# mainboardv3_1-clone.net
KiCad netlist of a schematic drawn in EAGLE
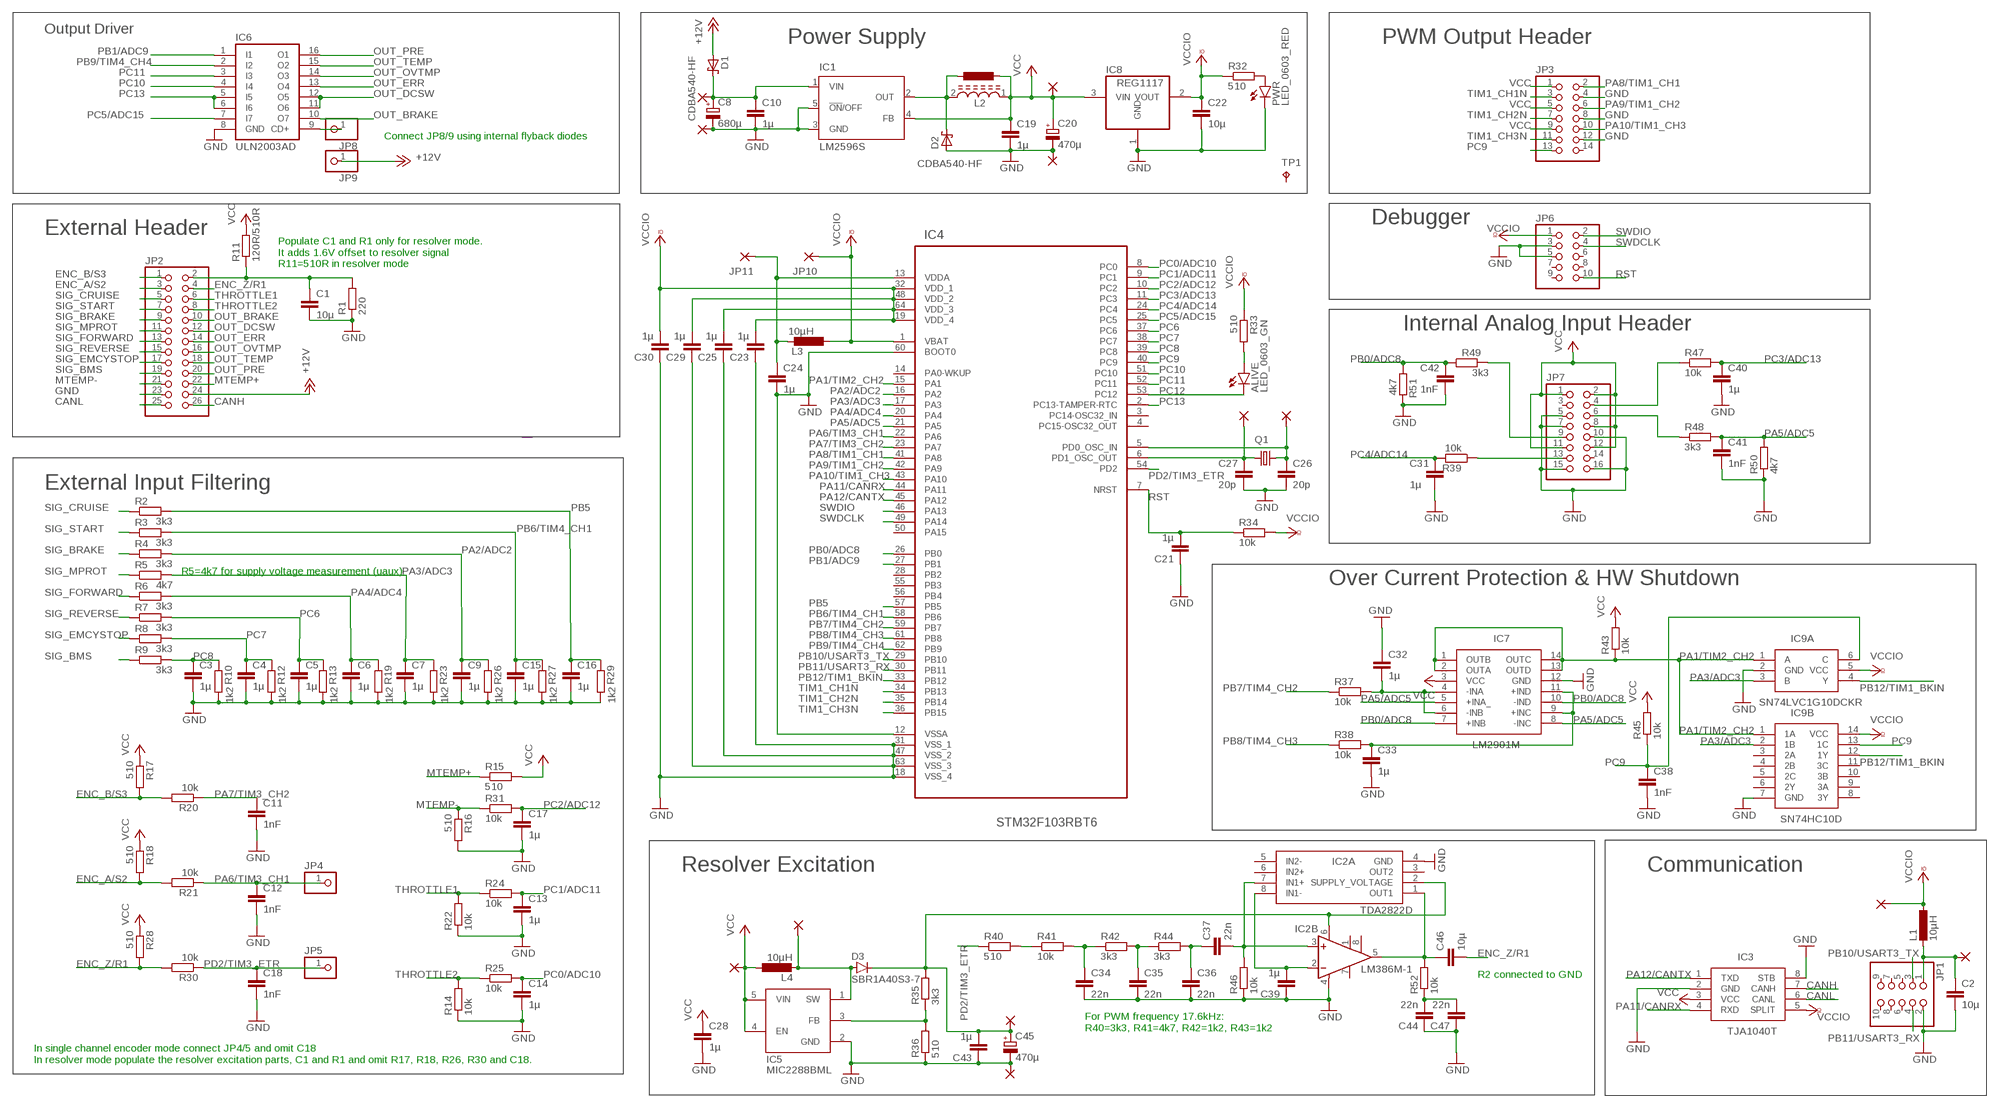
[diagram p0: schematic, sheet 1]

(export (version "E")
  (design (tool "Eeschema 10.0.6"))
  (components
    (comp (ref "ALIVE")
      (value "LED_0603_GN")
      (footprint "eagle-import:SML0805")
      (libsource (lib "eagle-import") (part "LEDSML0805"))
    )
    (comp (ref "C1")
      (value "10µ")
      (footprint "eagle-import:C0805K")
      (libsource (lib "eagle-import") (part "C-EUC0805K"))
    )
    (comp (ref "C2")
      (value "10µ")
      (footprint "eagle-import:C0805K")
      (libsource (lib "eagle-import") (part "C-EUC0805K"))
    )
    (comp (ref "C3")
      (value "1µ")
      (footprint "eagle-import:C0603K")
      (libsource (lib "eagle-import") (part "C-EUC0603K"))
    )
    (comp (ref "C4")
      (value "1µ")
      (footprint "eagle-import:C0603K")
      (libsource (lib "eagle-import") (part "C-EUC0603K"))
    )
    (comp (ref "C5")
      (value "1µ")
      (footprint "eagle-import:C0603K")
      (libsource (lib "eagle-import") (part "C-EUC0603K"))
    )
    (comp (ref "C6")
      (value "1µ")
      (footprint "eagle-import:C0603K")
      (libsource (lib "eagle-import") (part "C-EUC0603K"))
    )
    (comp (ref "C7")
      (value "1µ")
      (footprint "eagle-import:C0603K")
      (libsource (lib "eagle-import") (part "C-EUC0603K"))
    )
    (comp (ref "C8")
      (value "680µ")
      (footprint "eagle-import:153CLV-1014")
      (libsource (lib "eagle-import") (part "CPOL-EU153CLV-1014"))
    )
    (comp (ref "C9")
      (value "1µ")
      (footprint "eagle-import:C0603K")
      (libsource (lib "eagle-import") (part "C-EUC0603K"))
    )
    (comp (ref "C10")
      (value "1µ")
      (footprint "eagle-import:C0603K")
      (libsource (lib "eagle-import") (part "C-EUC0603K"))
    )
    (comp (ref "C11")
      (value "1nF")
      (footprint "eagle-import:C0603K")
      (libsource (lib "eagle-import") (part "C-EUC0603K"))
    )
    (comp (ref "C12")
      (value "1nF")
      (footprint "eagle-import:C0603K")
      (libsource (lib "eagle-import") (part "C-EUC0603K"))
    )
    (comp (ref "C13")
      (value "1µ")
      (footprint "eagle-import:C0603K")
      (libsource (lib "eagle-import") (part "C-EUC0603K"))
    )
    (comp (ref "C14")
      (value "1µ")
      (footprint "eagle-import:C0603K")
      (libsource (lib "eagle-import") (part "C-EUC0603K"))
    )
    (comp (ref "C15")
      (value "1µ")
      (footprint "eagle-import:C0603K")
      (libsource (lib "eagle-import") (part "C-EUC0603K"))
    )
    (comp (ref "C16")
      (value "1µ")
      (footprint "eagle-import:C0603K")
      (libsource (lib "eagle-import") (part "C-EUC0603K"))
    )
    (comp (ref "C17")
      (value "1µ")
      (footprint "eagle-import:C0603K")
      (libsource (lib "eagle-import") (part "C-EUC0603K"))
    )
    (comp (ref "C18")
      (value "1nF")
      (footprint "eagle-import:C0603K")
      (libsource (lib "eagle-import") (part "C-EUC0603K"))
    )
    (comp (ref "C19")
      (value "1µ")
      (footprint "eagle-import:C0603K")
      (libsource (lib "eagle-import") (part "C-EUC0603K"))
    )
    (comp (ref "C20")
      (value "470µ")
      (footprint "eagle-import:153CLV-0605")
      (libsource (lib "eagle-import") (part "CPOL-EU153CLV-0605"))
    )
    (comp (ref "C21")
      (value "1µ")
      (footprint "eagle-import:C0603K")
      (libsource (lib "eagle-import") (part "C-EUC0603K"))
    )
    (comp (ref "C22")
      (value "10µ")
      (footprint "eagle-import:C0805K")
      (libsource (lib "eagle-import") (part "C-EUC0805K"))
    )
    (comp (ref "C23")
      (value "1µ")
      (footprint "eagle-import:C0603K")
      (libsource (lib "eagle-import") (part "C-EUC0603K"))
    )
    (comp (ref "C24")
      (value "1µ")
      (footprint "eagle-import:C0603K")
      (libsource (lib "eagle-import") (part "C-EUC0603K"))
    )
    (comp (ref "C25")
      (value "1µ")
      (footprint "eagle-import:C0603K")
      (libsource (lib "eagle-import") (part "C-EUC0603K"))
    )
    (comp (ref "C26")
      (value "20p")
      (footprint "eagle-import:C0603K")
      (libsource (lib "eagle-import") (part "C-EUC0603K"))
    )
    (comp (ref "C27")
      (value "20p")
      (footprint "eagle-import:C0603K")
      (libsource (lib "eagle-import") (part "C-EUC0603K"))
    )
    (comp (ref "C28")
      (value "1µ")
      (footprint "eagle-import:C0603K")
      (libsource (lib "eagle-import") (part "C-EUC0603K"))
    )
    (comp (ref "C29")
      (value "1µ")
      (footprint "eagle-import:C0603K")
      (libsource (lib "eagle-import") (part "C-EUC0603K"))
    )
    (comp (ref "C30")
      (value "1µ")
      (footprint "eagle-import:C0603K")
      (libsource (lib "eagle-import") (part "C-EUC0603K"))
    )
    (comp (ref "C31")
      (value "1µ")
      (footprint "eagle-import:C0603K")
      (libsource (lib "eagle-import") (part "C-EUC0603K"))
    )
    (comp (ref "C32")
      (value "1µ")
      (footprint "eagle-import:C0603K")
      (libsource (lib "eagle-import") (part "C-EUC0603K"))
    )
    (comp (ref "C33")
      (value "1µ")
      (footprint "eagle-import:C0603K")
      (libsource (lib "eagle-import") (part "C-EUC0603K"))
    )
    (comp (ref "C34")
      (value "22n")
      (footprint "eagle-import:C0603K")
      (libsource (lib "eagle-import") (part "C-EUC0603K"))
    )
    (comp (ref "C35")
      (value "22n")
      (footprint "eagle-import:C0603K")
      (libsource (lib "eagle-import") (part "C-EUC0603K"))
    )
    (comp (ref "C36")
      (value "22n")
      (footprint "eagle-import:C0603K")
      (libsource (lib "eagle-import") (part "C-EUC0603K"))
    )
    (comp (ref "C37")
      (value "22n")
      (footprint "eagle-import:C0603K")
      (libsource (lib "eagle-import") (part "C-EUC0603K"))
    )
    (comp (ref "C38")
      (value "1nF")
      (footprint "eagle-import:C0603K")
      (libsource (lib "eagle-import") (part "C-EUC0603K"))
    )
    (comp (ref "C39")
      (value "1µ")
      (footprint "eagle-import:C0603K")
      (libsource (lib "eagle-import") (part "C-EUC0603K"))
    )
    (comp (ref "C40")
      (value "1µ")
      (footprint "eagle-import:C0603K")
      (libsource (lib "eagle-import") (part "C-EUC0603K"))
    )
    (comp (ref "C41")
      (value "1nF")
      (footprint "eagle-import:C0603K")
      (libsource (lib "eagle-import") (part "C-EUC0603K"))
    )
    (comp (ref "C42")
      (value "1nF")
      (footprint "eagle-import:C0603K")
      (libsource (lib "eagle-import") (part "C-EUC0603K"))
    )
    (comp (ref "C43")
      (value "1µ")
      (footprint "eagle-import:C0603K")
      (libsource (lib "eagle-import") (part "C-EUC0603K"))
    )
    (comp (ref "C44")
      (value "22n")
      (footprint "eagle-import:C0603K")
      (libsource (lib "eagle-import") (part "C-EUC0603K"))
    )
    (comp (ref "C45")
      (value "470µ")
      (footprint "eagle-import:153CLV-0605")
      (libsource (lib "eagle-import") (part "CPOL-EU153CLV-0605"))
    )
    (comp (ref "C46")
      (value "10µ")
      (footprint "eagle-import:C0805K")
      (libsource (lib "eagle-import") (part "C-EUC0805K"))
    )
    (comp (ref "C47")
      (value "22n")
      (footprint "eagle-import:C0603K")
      (libsource (lib "eagle-import") (part "C-EUC0603K"))
    )
    (comp (ref "D1")
      (value "CDBA540-HF")
      (footprint "eagle-import:SMB")
      (libsource (lib "eagle-import") (part "SCHOTTKY-DIODESMD"))
    )
    (comp (ref "D2")
      (value "CDBA540-HF")
      (footprint "eagle-import:SMB")
      (libsource (lib "eagle-import") (part "SCHOTTKY-DIODESMD"))
    )
    (comp (ref "D3")
      (value "SBR1A40S3-7")
      (footprint "eagle-import:SOD123")
      (libsource (lib "eagle-import") (part "D-SOD123"))
    )
    (comp (ref "IC1")
      (value "LM2596S")
      (footprint "eagle-import:TO263-5")
      (fields (field (name "MF") "NATIONAL SEMICONDUCTOR") (field (name "MPN") "LM2596S-ADJ/NOPB"))
      (libsource (lib "eagle-import") (part "LM2596S"))
    )
    (comp (ref "IC2A")
      (value "TDA2822D")
      (footprint "eagle-import:SOIC127P600X175-8N")
      (fields (field (name "MOUSER_PART_NUMBER") "511-TDA2822D") (field (name "RS_PART_NUMBER") "0426162P"))
      (libsource (lib "eagle-import") (part "TDA2822D"))
    )
    (comp (ref "IC2B")
      (value "LM386M-1")
      (footprint "eagle-import:SO08")
      (libsource (lib "eagle-import") (part "LM386?-M1"))
    )
    (comp (ref "IC3")
      (value "TJA1040T")
      (footprint "eagle-import:SOIC127P600X175-8N")
      (fields (field (name "MOUSER_PART_NUMBER") "4837547"))
      (libsource (lib "eagle-import") (part "TJA1040T"))
    )
    (comp (ref "IC4")
      (value "STM32F103RBT6")
      (footprint "eagle-import:QFP50P1200X1200X160-64N")
      (fields (field (name "DIGI-KEY_PART_NUMBER") "497-6066-ND") (field (name "MF") "STMicroelectronics"))
      (libsource (lib "eagle-import") (part "STM32F103RBT6"))
    )
    (comp (ref "IC5")
      (value "MIC2288BML")
      (footprint "eagle-import:SOT23-5L")
      (libsource (lib "eagle-import") (part "MIC2288BML"))
    )
    (comp (ref "IC6")
      (value "ULN2003AD")
      (footprint "eagle-import:SO16")
      (libsource (lib "eagle-import") (part "ULN2003AD"))
    )
    (comp (ref "IC7")
      (value "LM2901M")
      (footprint "eagle-import:SOP127P600X180-14N")
      (fields (field (name "MOUSER_PART_NUMBER") "4716204"))
      (libsource (lib "eagle-import") (part "LM2901M"))
    )
    (comp (ref "IC8")
      (value "REG1117")
      (footprint "eagle-import:SOT223")
      (libsource (lib "eagle-import") (part "REG1117"))
    )
    (comp (ref "IC9A")
      (value "SN74LVC1G10DCKR")
      (footprint "eagle-import:SOT65P210X110-6N")
      (fields
        (field (name "MOUSER_PART_NUMBER") "595-SN74LVC1G10DCKR")
        (field (name "RS_PART_NUMBER") "1627462")
      )
      (libsource (lib "eagle-import") (part "SN74LVC1G10DCKR"))
    )
    (comp (ref "IC9B")
      (value "SN74HC10D")
      (footprint "eagle-import:SOIC127P600X175-14N")
      (fields (field (name "MOUSER_PART_NUMBER") "595-SN74HC10D") (field (name "RS_PART_NUMBER") "6631896P"))
      (libsource (lib "eagle-import") (part "SN74HC10D"))
    )
    (comp (ref "JP1")
      (value "PINHD-2X5/90")
      (footprint "eagle-import:2X05_90")
      (libsource (lib "eagle-import") (part "PINHD-2X5/90"))
    )
    (comp (ref "JP2")
      (value "PINHD-2X13")
      (footprint "eagle-import:2X13")
      (libsource (lib "eagle-import") (part "PINHD-2X13"))
    )
    (comp (ref "JP3")
      (value "PINHD-2X7")
      (footprint "eagle-import:2X07")
      (libsource (lib "eagle-import") (part "PINHD-2X7"))
    )
    (comp (ref "JP4")
      (value "PINHD-1X1")
      (footprint "eagle-import:1X01")
      (libsource (lib "eagle-import") (part "PINHD-1X1"))
    )
    (comp (ref "JP5")
      (value "PINHD-1X1")
      (footprint "eagle-import:1X01")
      (libsource (lib "eagle-import") (part "PINHD-1X1"))
    )
    (comp (ref "JP6")
      (value "PINHD-2X5")
      (footprint "eagle-import:2X05")
      (libsource (lib "eagle-import") (part "PINHD-2X5"))
    )
    (comp (ref "JP7")
      (value "PINHD-2X8")
      (footprint "eagle-import:2X08")
      (libsource (lib "eagle-import") (part "PINHD-2X8"))
    )
    (comp (ref "JP8")
      (value "PINHD-1X1")
      (footprint "eagle-import:1X01")
      (libsource (lib "eagle-import") (part "PINHD-1X1"))
    )
    (comp (ref "JP9")
      (value "PINHD-1X1")
      (footprint "eagle-import:1X01")
      (libsource (lib "eagle-import") (part "PINHD-1X1"))
    )
    (comp (ref "JP10")
      (value "1,6/0,9")
      (footprint "eagle-import:1,6_0,9")
      (libsource (lib "eagle-import") (part "1,6/0,9"))
    )
    (comp (ref "JP11")
      (value "1,6/0,9")
      (footprint "eagle-import:1,6_0,9")
      (libsource (lib "eagle-import") (part "1,6/0,9"))
    )
    (comp (ref "JP12")
      (value "1,6/0,8")
      (footprint "eagle-import:1,6_0,8")
      (libsource (lib "eagle-import") (part "1,6/0,8"))
    )
    (comp (ref "JP13")
      (value "1,6/0,8")
      (footprint "eagle-import:1,6_0,8")
      (libsource (lib "eagle-import") (part "1,6/0,8"))
    )
    (comp (ref "JP14")
      (value "1,6/0,8")
      (footprint "eagle-import:1,6_0,8")
      (libsource (lib "eagle-import") (part "1,6/0,8"))
    )
    (comp (ref "JP15")
      (value "1,6/0,8")
      (footprint "eagle-import:1,6_0,8")
      (libsource (lib "eagle-import") (part "1,6/0,8"))
    )
    (comp (ref "JP16")
      (value "1,6/0,8")
      (footprint "eagle-import:1,6_0,8")
      (libsource (lib "eagle-import") (part "1,6/0,8"))
    )
    (comp (ref "JP17")
      (value "1,6/0,8")
      (footprint "eagle-import:1,6_0,8")
      (libsource (lib "eagle-import") (part "1,6/0,8"))
    )
    (comp (ref "L1")
      (value "10µH")
      (footprint "eagle-import:L3225M")
      (libsource (lib "eagle-import") (part "L-EUL3225M"))
    )
    (comp (ref "L2")
      (value "SRR1260-471K")
      (footprint "eagle-import:INDP125125X600N")
      (fields (field (name "MF") "Bourns"))
      (libsource (lib "eagle-import") (part "SRR1260-471K"))
    )
    (comp (ref "L3")
      (value "10µH")
      (footprint "eagle-import:L3225M")
      (libsource (lib "eagle-import") (part "L-EUL3225M"))
    )
    (comp (ref "L4")
      (value "10µH")
      (footprint "eagle-import:L3225M")
      (libsource (lib "eagle-import") (part "L-EUL3225M"))
    )
    (comp (ref "L5")
      (value "L-EUTJ3-U1")
      (footprint "eagle-import:TJ3-U1")
      (libsource (lib "eagle-import") (part "resistor_348_L-EUTJ3-U1"))
    )
    (comp (ref "PAD1")
      (value "1,6/0,9")
      (footprint "eagle-import:1,6_0,9")
      (libsource (lib "eagle-import") (part "1,6/0,9"))
    )
    (comp (ref "PAD2")
      (value "1,6/0,9")
      (footprint "eagle-import:1,6_0,9")
      (libsource (lib "eagle-import") (part "1,6/0,9"))
    )
    (comp (ref "PAD3")
      (value "1,6/0,8")
      (footprint "eagle-import:1,6_0,8")
      (libsource (lib "eagle-import") (part "1,6/0,8"))
    )
    (comp (ref "PAD4")
      (value "1,6/0,8")
      (footprint "eagle-import:1,6_0,8")
      (libsource (lib "eagle-import") (part "1,6/0,8"))
    )
    (comp (ref "PAD5")
      (value "1,6/0,8")
      (footprint "eagle-import:1,6_0,8")
      (libsource (lib "eagle-import") (part "1,6/0,8"))
    )
    (comp (ref "PAD6")
      (value "1,6/0,8")
      (footprint "eagle-import:1,6_0,8")
      (libsource (lib "eagle-import") (part "1,6/0,8"))
    )
    (comp (ref "PWR")
      (value "LED_0603_RED")
      (footprint "eagle-import:SML0805")
      (libsource (lib "eagle-import") (part "LEDSML0805"))
    )
    (comp (ref "Q1")
      (value "CSM-7X-DU")
      (footprint "eagle-import:CSM-7X-DU")
      (libsource (lib "eagle-import") (part "CSM-7X-DU"))
    )
    (comp (ref "R1")
      (value "220")
      (footprint "eagle-import:R0603")
      (libsource (lib "eagle-import") (part "R-EU_R0603"))
    )
    (comp (ref "R2")
      (value "3k3")
      (footprint "eagle-import:R0603")
      (libsource (lib "eagle-import") (part "R-EU_R0603"))
    )
    (comp (ref "R3")
      (value "3k3")
      (footprint "eagle-import:R0603")
      (libsource (lib "eagle-import") (part "R-EU_R0603"))
    )
    (comp (ref "R4")
      (value "3k3")
      (footprint "eagle-import:R0603")
      (libsource (lib "eagle-import") (part "R-EU_R0603"))
    )
    (comp (ref "R5")
      (value "4k7")
      (footprint "eagle-import:R0603")
      (libsource (lib "eagle-import") (part "R-EU_R0603"))
    )
    (comp (ref "R6")
      (value "3k3")
      (footprint "eagle-import:R0603")
      (libsource (lib "eagle-import") (part "R-EU_R0603"))
    )
    (comp (ref "R7")
      (value "3k3")
      (footprint "eagle-import:R0603")
      (libsource (lib "eagle-import") (part "R-EU_R0603"))
    )
    (comp (ref "R8")
      (value "3k3")
      (footprint "eagle-import:R0603")
      (libsource (lib "eagle-import") (part "R-EU_R0603"))
    )
    (comp (ref "R9")
      (value "3k3")
      (footprint "eagle-import:R0603")
      (libsource (lib "eagle-import") (part "R-EU_R0603"))
    )
    (comp (ref "R10")
      (value "1k2")
      (footprint "eagle-import:R0603")
      (libsource (lib "eagle-import") (part "R-EU_R0603"))
    )
    (comp (ref "R11")
      (value "120R/510R")
      (footprint "eagle-import:R0603")
      (libsource (lib "eagle-import") (part "R-EU_R0603"))
    )
    (comp (ref "R12")
      (value "1k2")
      (footprint "eagle-import:R0603")
      (libsource (lib "eagle-import") (part "R-EU_R0603"))
    )
    (comp (ref "R13")
      (value "1k2")
      (footprint "eagle-import:R0603")
      (libsource (lib "eagle-import") (part "R-EU_R0603"))
    )
    (comp (ref "R14")
      (value "10k")
      (footprint "eagle-import:R0603")
      (libsource (lib "eagle-import") (part "R-EU_R0603"))
    )
    (comp (ref "R15")
      (value "510")
      (footprint "eagle-import:R0603")
      (libsource (lib "eagle-import") (part "R-EU_R0603"))
    )
    (comp (ref "R16")
      (value "510")
      (footprint "eagle-import:R0603")
      (libsource (lib "eagle-import") (part "R-EU_R0603"))
    )
    (comp (ref "R17")
      (value "510")
      (footprint "eagle-import:R0603")
      (libsource (lib "eagle-import") (part "R-EU_R0603"))
    )
    (comp (ref "R18")
      (value "510")
      (footprint "eagle-import:R0603")
      (libsource (lib "eagle-import") (part "R-EU_R0603"))
    )
    (comp (ref "R19")
      (value "1k2")
      (footprint "eagle-import:R0603")
      (libsource (lib "eagle-import") (part "R-EU_R0603"))
    )
    (comp (ref "R20")
      (value "10k")
      (footprint "eagle-import:R0603")
      (libsource (lib "eagle-import") (part "R-EU_R0603"))
    )
    (comp (ref "R21")
      (value "10k")
      (footprint "eagle-import:R0603")
      (libsource (lib "eagle-import") (part "R-EU_R0603"))
    )
    (comp (ref "R22")
      (value "10k")
      (footprint "eagle-import:R0603")
      (libsource (lib "eagle-import") (part "R-EU_R0603"))
    )
    (comp (ref "R23")
      (value "1k2")
      (footprint "eagle-import:R0603")
      (libsource (lib "eagle-import") (part "R-EU_R0603"))
    )
    (comp (ref "R24")
      (value "10k")
      (footprint "eagle-import:R0603")
      (libsource (lib "eagle-import") (part "R-EU_R0603"))
    )
    (comp (ref "R25")
      (value "10k")
      (footprint "eagle-import:R0603")
      (libsource (lib "eagle-import") (part "R-EU_R0603"))
    )
    (comp (ref "R26")
      (value "1k2")
      (footprint "eagle-import:R0603")
      (libsource (lib "eagle-import") (part "R-EU_R0603"))
    )
    (comp (ref "R27")
      (value "1k2")
      (footprint "eagle-import:R0603")
      (libsource (lib "eagle-import") (part "R-EU_R0603"))
    )
    (comp (ref "R28")
      (value "510")
      (footprint "eagle-import:R0603")
      (libsource (lib "eagle-import") (part "R-EU_R0603"))
    )
    (comp (ref "R29")
      (value "1k2")
      (footprint "eagle-import:R0603")
      (libsource (lib "eagle-import") (part "R-EU_R0603"))
    )
    (comp (ref "R30")
      (value "10k")
      (footprint "eagle-import:R0603")
      (libsource (lib "eagle-import") (part "R-EU_R0603"))
    )
    (comp (ref "R31")
      (value "10k")
      (footprint "eagle-import:R0603")
      (libsource (lib "eagle-import") (part "R-EU_R0603"))
    )
    (comp (ref "R32")
      (value "510")
      (footprint "eagle-import:R0603")
      (libsource (lib "eagle-import") (part "R-EU_R0603"))
    )
    (comp (ref "R33")
      (value "510")
      (footprint "eagle-import:R0603")
      (libsource (lib "eagle-import") (part "R-EU_R0603"))
    )
    (comp (ref "R34")
      (value "10k")
      (footprint "eagle-import:R0603")
      (libsource (lib "eagle-import") (part "R-EU_R0603"))
    )
    (comp (ref "R35")
      (value "3k3")
      (footprint "eagle-import:R0603")
      (libsource (lib "eagle-import") (part "R-EU_R0603"))
    )
    (comp (ref "R36")
      (value "510")
      (footprint "eagle-import:R0603")
      (libsource (lib "eagle-import") (part "R-EU_R0603"))
    )
    (comp (ref "R37")
      (value "10k")
      (footprint "eagle-import:R0603")
      (libsource (lib "eagle-import") (part "R-EU_R0603"))
    )
    (comp (ref "R38")
      (value "10k")
      (footprint "eagle-import:R0603")
      (libsource (lib "eagle-import") (part "R-EU_R0603"))
    )
    (comp (ref "R39")
      (value "10k")
      (footprint "eagle-import:R0603")
      (libsource (lib "eagle-import") (part "R-EU_R0603"))
    )
    (comp (ref "R40")
      (value "510")
      (footprint "eagle-import:R0603")
      (libsource (lib "eagle-import") (part "R-EU_R0603"))
    )
    (comp (ref "R41")
      (value "10k")
      (footprint "eagle-import:R0603")
      (libsource (lib "eagle-import") (part "R-EU_R0603"))
    )
    (comp (ref "R42")
      (value "3k3")
      (footprint "eagle-import:R0603")
      (libsource (lib "eagle-import") (part "R-EU_R0603"))
    )
    (comp (ref "R43")
      (value "10k")
      (footprint "eagle-import:R0603")
      (libsource (lib "eagle-import") (part "R-EU_R0603"))
    )
    (comp (ref "R44")
      (value "3k3")
      (footprint "eagle-import:R0603")
      (libsource (lib "eagle-import") (part "R-EU_R0603"))
    )
    (comp (ref "R45")
      (value "10k")
      (footprint "eagle-import:R0603")
      (libsource (lib "eagle-import") (part "R-EU_R0603"))
    )
    (comp (ref "R46")
      (value "10k")
      (footprint "eagle-import:R0603")
      (libsource (lib "eagle-import") (part "R-EU_R0603"))
    )
    (comp (ref "R47")
      (value "10k")
      (footprint "eagle-import:R0603")
      (libsource (lib "eagle-import") (part "R-EU_R0603"))
    )
    (comp (ref "R48")
      (value "3k3")
      (footprint "eagle-import:R0603")
      (libsource (lib "eagle-import") (part "R-EU_R0603"))
    )
    (comp (ref "R49")
      (value "3k3")
      (footprint "eagle-import:R0603")
      (libsource (lib "eagle-import") (part "R-EU_R0603"))
    )
    (comp (ref "R50")
      (value "4k7")
      (footprint "eagle-import:R0603")
      (libsource (lib "eagle-import") (part "R-EU_R0603"))
    )
    (comp (ref "R51")
      (value "4k7")
      (footprint "eagle-import:R0603")
      (libsource (lib "eagle-import") (part "R-EU_R0603"))
    )
    (comp (ref "R52")
      (value "10k")
      (footprint "eagle-import:R0603")
      (libsource (lib "eagle-import") (part "R-EU_R0603"))
    )
    (comp (ref "TP1")
      (value "TPB1,27")
      (footprint "eagle-import:B1,27")
      (libsource (lib "eagle-import") (part "TPB1,27"))
    )
  )
  (nets
    (net (code "1") (name "+12V") (class "Default")
      (node (ref "D1") (pin "A") (pinfunction "A_A") (pintype "passive"))
      (node (ref "JP2") (pin "24") (pinfunction "24_24") (pintype "passive"))
      (node (ref "JP9") (pin "1") (pinfunction "1_1") (pintype "passive"))
    )
    (net (code "2") (name "/CANH") (class "Default")
      (node (ref "IC3") (pin "7") (pinfunction "CANH_7") (pintype "bidirectional"))
      (node (ref "JP2") (pin "26") (pinfunction "26_26") (pintype "passive"))
    )
    (net (code "3") (name "/CANL") (class "Default")
      (node (ref "IC3") (pin "6") (pinfunction "CANL_6") (pintype "bidirectional"))
      (node (ref "JP2") (pin "25") (pinfunction "25_25") (pintype "passive"))
    )
    (net (code "4") (name "/ENC_A{slash}S2") (class "Default")
      (node (ref "JP2") (pin "3") (pinfunction "3_3") (pintype "passive"))
      (node (ref "R18") (pin "2") (pinfunction "2_2") (pintype "passive"))
      (node (ref "R21") (pin "2") (pinfunction "2_2") (pintype "passive"))
    )
    (net (code "5") (name "/ENC_B{slash}S3") (class "Default")
      (node (ref "JP2") (pin "1") (pinfunction "1_1") (pintype "passive"))
      (node (ref "R17") (pin "2") (pinfunction "2_2") (pintype "passive"))
      (node (ref "R20") (pin "2") (pinfunction "2_2") (pintype "passive"))
    )
    (net (code "6") (name "/ENC_Z{slash}R1") (class "Default")
      (node (ref "C46") (pin "2") (pinfunction "2_2") (pintype "passive"))
      (node (ref "JP2") (pin "4") (pinfunction "4_4") (pintype "passive"))
      (node (ref "R28") (pin "2") (pinfunction "2_2") (pintype "passive"))
      (node (ref "R30") (pin "2") (pinfunction "2_2") (pintype "passive"))
    )
    (net (code "7") (name "/MTEMP+") (class "Default")
      (node (ref "JP2") (pin "22") (pinfunction "22_22") (pintype "passive"))
      (node (ref "R15") (pin "1") (pinfunction "1_1") (pintype "passive"))
    )
    (net (code "8") (name "/MTEMP-") (class "Default")
      (node (ref "JP2") (pin "21") (pinfunction "21_21") (pintype "passive"))
      (node (ref "R16") (pin "1") (pinfunction "1_1") (pintype "passive"))
      (node (ref "R31") (pin "1") (pinfunction "1_1") (pintype "passive"))
    )
    (net (code "9") (name "/OUT_BRAKE") (class "Default")
      (node (ref "IC6") (pin "10") (pinfunction "O7_10") (pintype "open_collector"))
      (node (ref "JP2") (pin "10") (pinfunction "10_10") (pintype "passive"))
    )
    (net (code "10") (name "/OUT_DCSW") (class "Default")
      (node (ref "IC6") (pin "11") (pinfunction "O6_11") (pintype "open_collector"))
      (node (ref "IC6") (pin "12") (pinfunction "O5_12") (pintype "open_collector"))
      (node (ref "JP2") (pin "12") (pinfunction "12_12") (pintype "passive"))
    )
    (net (code "11") (name "/OUT_ERR") (class "Default")
      (node (ref "IC6") (pin "13") (pinfunction "O4_13") (pintype "open_collector"))
      (node (ref "JP2") (pin "14") (pinfunction "14_14") (pintype "passive"))
    )
    (net (code "12") (name "/OUT_OVTMP") (class "Default")
      (node (ref "IC6") (pin "14") (pinfunction "O3_14") (pintype "open_collector"))
      (node (ref "JP2") (pin "16") (pinfunction "16_16") (pintype "passive"))
    )
    (net (code "13") (name "/OUT_PRE") (class "Default")
      (node (ref "IC6") (pin "16") (pinfunction "O1_16") (pintype "open_collector"))
      (node (ref "JP2") (pin "20") (pinfunction "20_20") (pintype "passive"))
    )
    (net (code "14") (name "/OUT_TEMP") (class "Default")
      (node (ref "IC6") (pin "15") (pinfunction "O2_15") (pintype "open_collector"))
      (node (ref "JP2") (pin "18") (pinfunction "18_18") (pintype "passive"))
    )
    (net (code "15") (name "/PA1{slash}TIM2_CH2") (class "Default")
      (node (ref "IC4") (pin "15") (pinfunction "PA1_15") (pintype "bidirectional"))
      (node (ref "IC7") (pin "1") (pinfunction "OUTB_1") (pintype "bidirectional"))
      (node (ref "IC7") (pin "13") (pinfunction "OUTD_13") (pintype "bidirectional"))
      (node (ref "IC7") (pin "14") (pinfunction "OUTC_14") (pintype "bidirectional"))
      (node (ref "IC7") (pin "2") (pinfunction "OUTA_2") (pintype "bidirectional"))
      (node (ref "IC9A") (pin "1") (pinfunction "A_1") (pintype "bidirectional"))
      (node (ref "IC9B") (pin "1") (pinfunction "1A_1") (pintype "bidirectional"))
      (node (ref "R43") (pin "1") (pinfunction "1_1") (pintype "passive"))
    )
    (net (code "16") (name "/PA2{slash}ADC2") (class "Default")
      (node (ref "C9") (pin "1") (pinfunction "1_1") (pintype "passive"))
      (node (ref "IC4") (pin "16") (pinfunction "PA2_16") (pintype "bidirectional"))
      (node (ref "R26") (pin "1") (pinfunction "1_1") (pintype "passive"))
      (node (ref "R4") (pin "2") (pinfunction "2_2") (pintype "passive"))
    )
    (net (code "17") (name "/PA3{slash}ADC3") (class "Default")
      (node (ref "C7") (pin "1") (pinfunction "1_1") (pintype "passive"))
      (node (ref "IC4") (pin "17") (pinfunction "PA3_17") (pintype "bidirectional"))
      (node (ref "IC9A") (pin "3") (pinfunction "B_3") (pintype "bidirectional"))
      (node (ref "IC9B") (pin "2") (pinfunction "1B_2") (pintype "bidirectional"))
      (node (ref "R23") (pin "1") (pinfunction "1_1") (pintype "passive"))
      (node (ref "R5") (pin "2") (pinfunction "2_2") (pintype "passive"))
    )
    (net (code "18") (name "/PA4{slash}ADC4") (class "Default")
      (node (ref "C6") (pin "1") (pinfunction "1_1") (pintype "passive"))
      (node (ref "IC4") (pin "20") (pinfunction "PA4_20") (pintype "bidirectional"))
      (node (ref "R19") (pin "1") (pinfunction "1_1") (pintype "passive"))
      (node (ref "R6") (pin "2") (pinfunction "2_2") (pintype "passive"))
    )
    (net (code "19") (name "/PA5{slash}ADC5") (class "Default")
      (node (ref "C41") (pin "1") (pinfunction "1_1") (pintype "passive"))
      (node (ref "IC4") (pin "21") (pinfunction "PA5_21") (pintype "bidirectional"))
      (node (ref "IC7") (pin "5") (pinfunction "+INA__5") (pintype "bidirectional"))
      (node (ref "IC7") (pin "8") (pinfunction "-INC_8") (pintype "bidirectional"))
      (node (ref "R48") (pin "2") (pinfunction "2_2") (pintype "passive"))
      (node (ref "R50") (pin "2") (pinfunction "2_2") (pintype "passive"))
    )
    (net (code "20") (name "/PA6{slash}TIM3_CH1") (class "Default")
      (node (ref "C12") (pin "1") (pinfunction "1_1") (pintype "passive"))
      (node (ref "IC4") (pin "22") (pinfunction "PA6_22") (pintype "bidirectional"))
      (node (ref "JP4") (pin "1") (pinfunction "1_1") (pintype "passive"))
      (node (ref "R21") (pin "1") (pinfunction "1_1") (pintype "passive"))
    )
    (net (code "21") (name "/PA7{slash}TIM3_CH2") (class "Default")
      (node (ref "C11") (pin "1") (pinfunction "1_1") (pintype "passive"))
      (node (ref "IC4") (pin "23") (pinfunction "PA7_23") (pintype "bidirectional"))
      (node (ref "R20") (pin "1") (pinfunction "1_1") (pintype "passive"))
    )
    (net (code "22") (name "/PA8{slash}TIM1_CH1") (class "Default")
      (node (ref "IC4") (pin "41") (pinfunction "PA8_41") (pintype "bidirectional"))
      (node (ref "JP3") (pin "2") (pinfunction "2_2") (pintype "passive"))
    )
    (net (code "23") (name "/PA9{slash}TIM1_CH2") (class "Default")
      (node (ref "IC4") (pin "42") (pinfunction "PA9_42") (pintype "bidirectional"))
      (node (ref "JP3") (pin "6") (pinfunction "6_6") (pintype "passive"))
    )
    (net (code "24") (name "/PA10{slash}TIM1_CH3") (class "Default")
      (node (ref "IC4") (pin "43") (pinfunction "PA10_43") (pintype "bidirectional"))
      (node (ref "JP3") (pin "10") (pinfunction "10_10") (pintype "passive"))
    )
    (net (code "25") (name "/PA11{slash}CANRX") (class "Default")
      (node (ref "IC3") (pin "4") (pinfunction "RXD_4") (pintype "output"))
      (node (ref "IC4") (pin "44") (pinfunction "PA11_44") (pintype "bidirectional"))
    )
    (net (code "26") (name "/PA12{slash}CANTX") (class "Default")
      (node (ref "IC3") (pin "1") (pinfunction "TXD_1") (pintype "input"))
      (node (ref "IC4") (pin "45") (pinfunction "PA12_45") (pintype "bidirectional"))
    )
    (net (code "27") (name "/PB0{slash}ADC8") (class "Default")
      (node (ref "C42") (pin "1") (pinfunction "1_1") (pintype "passive"))
      (node (ref "IC4") (pin "26") (pinfunction "PB0_26") (pintype "bidirectional"))
      (node (ref "IC7") (pin "10") (pinfunction "-IND_10") (pintype "bidirectional"))
      (node (ref "IC7") (pin "7") (pinfunction "+INB_7") (pintype "bidirectional"))
      (node (ref "R49") (pin "1") (pinfunction "1_1") (pintype "passive"))
      (node (ref "R51") (pin "1") (pinfunction "1_1") (pintype "passive"))
    )
    (net (code "28") (name "/PB1{slash}ADC9") (class "Default")
      (node (ref "IC4") (pin "27") (pinfunction "PB1_27") (pintype "bidirectional"))
      (node (ref "IC6") (pin "1") (pinfunction "I1_1") (pintype "input"))
    )
    (net (code "29") (name "/PB5") (class "Default")
      (node (ref "C16") (pin "1") (pinfunction "1_1") (pintype "passive"))
      (node (ref "IC4") (pin "57") (pinfunction "PB5_57") (pintype "bidirectional"))
      (node (ref "R2") (pin "2") (pinfunction "2_2") (pintype "passive"))
      (node (ref "R29") (pin "1") (pinfunction "1_1") (pintype "passive"))
    )
    (net (code "30") (name "/PB6{slash}TIM4_CH1") (class "Default")
      (node (ref "C15") (pin "1") (pinfunction "1_1") (pintype "passive"))
      (node (ref "IC4") (pin "58") (pinfunction "PB6_58") (pintype "bidirectional"))
      (node (ref "R27") (pin "1") (pinfunction "1_1") (pintype "passive"))
      (node (ref "R3") (pin "2") (pinfunction "2_2") (pintype "passive"))
    )
    (net (code "31") (name "/PB7{slash}TIM4_CH2") (class "Default")
      (node (ref "IC4") (pin "59") (pinfunction "PB7_59") (pintype "bidirectional"))
      (node (ref "R37") (pin "1") (pinfunction "1_1") (pintype "passive"))
    )
    (net (code "32") (name "/PB8{slash}TIM4_CH3") (class "Default")
      (node (ref "IC4") (pin "61") (pinfunction "PB8_61") (pintype "bidirectional"))
      (node (ref "R38") (pin "1") (pinfunction "1_1") (pintype "passive"))
    )
    (net (code "33") (name "/PB9{slash}TIM4_CH4") (class "Default")
      (node (ref "IC4") (pin "62") (pinfunction "PB9_62") (pintype "bidirectional"))
      (node (ref "IC6") (pin "2") (pinfunction "I2_2") (pintype "input"))
    )
    (net (code "34") (name "/PB10{slash}USART3_TX") (class "Default")
      (node (ref "IC4") (pin "29") (pinfunction "PB10_29") (pintype "bidirectional"))
      (node (ref "JP1") (pin "3") (pinfunction "3_3") (pintype "passive"))
    )
    (net (code "35") (name "/PB11{slash}USART3_RX") (class "Default")
      (node (ref "IC4") (pin "30") (pinfunction "PB11_30") (pintype "bidirectional"))
      (node (ref "JP1") (pin "4") (pinfunction "4_4") (pintype "passive"))
    )
    (net (code "36") (name "/PB12{slash}TIM1_BKIN") (class "Default")
      (node (ref "IC4") (pin "33") (pinfunction "PB12_33") (pintype "bidirectional"))
      (node (ref "IC9A") (pin "4") (pinfunction "Y_4") (pintype "bidirectional"))
      (node (ref "IC9B") (pin "12") (pinfunction "1Y_12") (pintype "bidirectional"))
    )
    (net (code "37") (name "/PC0{slash}ADC10") (class "Default")
      (node (ref "C14") (pin "1") (pinfunction "1_1") (pintype "passive"))
      (node (ref "IC4") (pin "8") (pinfunction "PC0_8") (pintype "bidirectional"))
      (node (ref "R25") (pin "2") (pinfunction "2_2") (pintype "passive"))
    )
    (net (code "38") (name "/PC1{slash}ADC11") (class "Default")
      (node (ref "C13") (pin "1") (pinfunction "1_1") (pintype "passive"))
      (node (ref "IC4") (pin "9") (pinfunction "PC1_9") (pintype "bidirectional"))
      (node (ref "R24") (pin "2") (pinfunction "2_2") (pintype "passive"))
    )
    (net (code "39") (name "/PC2{slash}ADC12") (class "Default")
      (node (ref "C17") (pin "1") (pinfunction "1_1") (pintype "passive"))
      (node (ref "IC4") (pin "10") (pinfunction "PC2_10") (pintype "bidirectional"))
      (node (ref "R31") (pin "2") (pinfunction "2_2") (pintype "passive"))
    )
    (net (code "40") (name "/PC3{slash}ADC13") (class "Default")
      (node (ref "C40") (pin "1") (pinfunction "1_1") (pintype "passive"))
      (node (ref "IC4") (pin "11") (pinfunction "PC3_11") (pintype "bidirectional"))
      (node (ref "R47") (pin "2") (pinfunction "2_2") (pintype "passive"))
    )
    (net (code "41") (name "/PC4{slash}ADC14") (class "Default")
      (node (ref "C31") (pin "1") (pinfunction "1_1") (pintype "passive"))
      (node (ref "IC4") (pin "24") (pinfunction "PC4_24") (pintype "bidirectional"))
      (node (ref "R39") (pin "2") (pinfunction "2_2") (pintype "passive"))
    )
    (net (code "42") (name "/PC5{slash}ADC15") (class "Default")
      (node (ref "IC4") (pin "25") (pinfunction "PC5_25") (pintype "bidirectional"))
      (node (ref "IC6") (pin "7") (pinfunction "I7_7") (pintype "input"))
    )
    (net (code "43") (name "/PC6") (class "Default")
      (node (ref "C5") (pin "1") (pinfunction "1_1") (pintype "passive"))
      (node (ref "IC4") (pin "37") (pinfunction "PC6_37") (pintype "bidirectional"))
      (node (ref "R13") (pin "1") (pinfunction "1_1") (pintype "passive"))
      (node (ref "R7") (pin "2") (pinfunction "2_2") (pintype "passive"))
    )
    (net (code "44") (name "/PC7") (class "Default")
      (node (ref "C4") (pin "1") (pinfunction "1_1") (pintype "passive"))
      (node (ref "IC4") (pin "38") (pinfunction "PC7_38") (pintype "bidirectional"))
      (node (ref "R12") (pin "1") (pinfunction "1_1") (pintype "passive"))
      (node (ref "R8") (pin "2") (pinfunction "2_2") (pintype "passive"))
    )
    (net (code "45") (name "/PC8") (class "Default")
      (node (ref "C3") (pin "1") (pinfunction "1_1") (pintype "passive"))
      (node (ref "IC4") (pin "39") (pinfunction "PC8_39") (pintype "bidirectional"))
      (node (ref "R10") (pin "1") (pinfunction "1_1") (pintype "passive"))
      (node (ref "R9") (pin "2") (pinfunction "2_2") (pintype "passive"))
    )
    (net (code "46") (name "/PC9") (class "Default")
      (node (ref "C38") (pin "1") (pinfunction "1_1") (pintype "passive"))
      (node (ref "IC4") (pin "40") (pinfunction "PC9_40") (pintype "bidirectional"))
      (node (ref "IC9A") (pin "6") (pinfunction "C_6") (pintype "bidirectional"))
      (node (ref "IC9B") (pin "13") (pinfunction "1C_13") (pintype "bidirectional"))
      (node (ref "JP3") (pin "13") (pinfunction "13_13") (pintype "passive"))
      (node (ref "R45") (pin "1") (pinfunction "1_1") (pintype "passive"))
    )
    (net (code "47") (name "/PC10") (class "Default")
      (node (ref "IC4") (pin "51") (pinfunction "PC10_51") (pintype "bidirectional"))
      (node (ref "IC6") (pin "4") (pinfunction "I4_4") (pintype "input"))
    )
    (net (code "48") (name "/PC11") (class "Default")
      (node (ref "IC4") (pin "52") (pinfunction "PC11_52") (pintype "bidirectional"))
      (node (ref "IC6") (pin "3") (pinfunction "I3_3") (pintype "input"))
    )
    (net (code "49") (name "/PC12") (class "Default")
      (node (ref "ALIVE") (pin "C") (pinfunction "C_C") (pintype "passive"))
      (node (ref "IC4") (pin "53") (pinfunction "PC12_53") (pintype "bidirectional"))
    )
    (net (code "50") (name "/PC13") (class "Default")
      (node (ref "IC4") (pin "2") (pinfunction "PC13-TAMPER-RTC_2") (pintype "bidirectional"))
      (node (ref "IC6") (pin "5") (pinfunction "I5_5") (pintype "input"))
      (node (ref "IC6") (pin "6") (pinfunction "I6_6") (pintype "input"))
    )
    (net (code "51") (name "/PD2{slash}TIM3_ETR") (class "Default")
      (node (ref "C18") (pin "1") (pinfunction "1_1") (pintype "passive"))
      (node (ref "IC4") (pin "54") (pinfunction "PD2_54") (pintype "bidirectional"))
      (node (ref "JP5") (pin "1") (pinfunction "1_1") (pintype "passive"))
      (node (ref "R30") (pin "1") (pinfunction "1_1") (pintype "passive"))
      (node (ref "R40") (pin "1") (pinfunction "1_1") (pintype "passive"))
    )
    (net (code "52") (name "/RST") (class "Default")
      (node (ref "C21") (pin "2") (pinfunction "2_2") (pintype "passive"))
      (node (ref "IC4") (pin "7") (pinfunction "NRST_7") (pintype "bidirectional"))
      (node (ref "JP6") (pin "10") (pinfunction "10_10") (pintype "passive"))
      (node (ref "R34") (pin "1") (pinfunction "1_1") (pintype "passive"))
    )
    (net (code "53") (name "/SIG_BMS") (class "Default")
      (node (ref "JP2") (pin "19") (pinfunction "19_19") (pintype "passive"))
      (node (ref "R9") (pin "1") (pinfunction "1_1") (pintype "passive"))
    )
    (net (code "54") (name "/SIG_BRAKE") (class "Default")
      (node (ref "JP2") (pin "9") (pinfunction "9_9") (pintype "passive"))
      (node (ref "R4") (pin "1") (pinfunction "1_1") (pintype "passive"))
    )
    (net (code "55") (name "/SIG_CRUISE") (class "Default")
      (node (ref "JP2") (pin "5") (pinfunction "5_5") (pintype "passive"))
      (node (ref "R2") (pin "1") (pinfunction "1_1") (pintype "passive"))
    )
    (net (code "56") (name "/SIG_EMCYSTOP") (class "Default")
      (node (ref "JP2") (pin "17") (pinfunction "17_17") (pintype "passive"))
      (node (ref "R8") (pin "1") (pinfunction "1_1") (pintype "passive"))
    )
    (net (code "57") (name "/SIG_FORWARD") (class "Default")
      (node (ref "JP2") (pin "13") (pinfunction "13_13") (pintype "passive"))
      (node (ref "R6") (pin "1") (pinfunction "1_1") (pintype "passive"))
    )
    (net (code "58") (name "/SIG_MPROT") (class "Default")
      (node (ref "JP2") (pin "11") (pinfunction "11_11") (pintype "passive"))
      (node (ref "R5") (pin "1") (pinfunction "1_1") (pintype "passive"))
    )
    (net (code "59") (name "/SIG_REVERSE") (class "Default")
      (node (ref "JP2") (pin "15") (pinfunction "15_15") (pintype "passive"))
      (node (ref "R7") (pin "1") (pinfunction "1_1") (pintype "passive"))
    )
    (net (code "60") (name "/SIG_START") (class "Default")
      (node (ref "JP2") (pin "7") (pinfunction "7_7") (pintype "passive"))
      (node (ref "R3") (pin "1") (pinfunction "1_1") (pintype "passive"))
    )
    (net (code "61") (name "/SWDCLK") (class "Default")
      (node (ref "IC4") (pin "49") (pinfunction "PA14_49") (pintype "bidirectional"))
      (node (ref "JP6") (pin "4") (pinfunction "4_4") (pintype "passive"))
    )
    (net (code "62") (name "/SWDIO") (class "Default")
      (node (ref "IC4") (pin "46") (pinfunction "PA13_46") (pintype "bidirectional"))
      (node (ref "JP6") (pin "2") (pinfunction "2_2") (pintype "passive"))
    )
    (net (code "63") (name "/THROTTLE1") (class "Default")
      (node (ref "JP2") (pin "6") (pinfunction "6_6") (pintype "passive"))
      (node (ref "R22") (pin "2") (pinfunction "2_2") (pintype "passive"))
      (node (ref "R24") (pin "1") (pinfunction "1_1") (pintype "passive"))
    )
    (net (code "64") (name "/THROTTLE2") (class "Default")
      (node (ref "JP2") (pin "8") (pinfunction "8_8") (pintype "passive"))
      (node (ref "R14") (pin "2") (pinfunction "2_2") (pintype "passive"))
      (node (ref "R25") (pin "1") (pinfunction "1_1") (pintype "passive"))
    )
    (net (code "65") (name "/TIM1_CH1N") (class "Default")
      (node (ref "IC4") (pin "34") (pinfunction "PB13_34") (pintype "bidirectional"))
      (node (ref "JP3") (pin "3") (pinfunction "3_3") (pintype "passive"))
    )
    (net (code "66") (name "/TIM1_CH2N") (class "Default")
      (node (ref "IC4") (pin "35") (pinfunction "PB14_35") (pintype "bidirectional"))
      (node (ref "JP3") (pin "7") (pinfunction "7_7") (pintype "passive"))
    )
    (net (code "67") (name "/TIM1_CH3N") (class "Default")
      (node (ref "IC4") (pin "36") (pinfunction "PB15_36") (pintype "bidirectional"))
      (node (ref "JP3") (pin "11") (pinfunction "11_11") (pintype "passive"))
    )
    (net (code "68") (name "GND") (class "Default")
      (node (ref "C1") (pin "2") (pinfunction "2_2") (pintype "passive"))
      (node (ref "C10") (pin "2") (pinfunction "2_2") (pintype "passive"))
      (node (ref "C11") (pin "2") (pinfunction "2_2") (pintype "passive"))
      (node (ref "C12") (pin "2") (pinfunction "2_2") (pintype "passive"))
      (node (ref "C13") (pin "2") (pinfunction "2_2") (pintype "passive"))
      (node (ref "C14") (pin "2") (pinfunction "2_2") (pintype "passive"))
      (node (ref "C15") (pin "2") (pinfunction "2_2") (pintype "passive"))
      (node (ref "C16") (pin "2") (pinfunction "2_2") (pintype "passive"))
      (node (ref "C17") (pin "2") (pinfunction "2_2") (pintype "passive"))
      (node (ref "C18") (pin "2") (pinfunction "2_2") (pintype "passive"))
      (node (ref "C19") (pin "2") (pinfunction "2_2") (pintype "passive"))
      (node (ref "C2") (pin "2") (pinfunction "2_2") (pintype "passive"))
      (node (ref "C20") (pin "-") (pinfunction "-_-") (pintype "passive"))
      (node (ref "C21") (pin "1") (pinfunction "1_1") (pintype "passive"))
      (node (ref "C22") (pin "2") (pinfunction "2_2") (pintype "passive"))
      (node (ref "C23") (pin "1") (pinfunction "1_1") (pintype "passive"))
      (node (ref "C24") (pin "2") (pinfunction "2_2") (pintype "passive"))
      (node (ref "C25") (pin "1") (pinfunction "1_1") (pintype "passive"))
      (node (ref "C26") (pin "2") (pinfunction "2_2") (pintype "passive"))
      (node (ref "C27") (pin "2") (pinfunction "2_2") (pintype "passive"))
      (node (ref "C28") (pin "2") (pinfunction "2_2") (pintype "passive"))
      (node (ref "C29") (pin "1") (pinfunction "1_1") (pintype "passive"))
      (node (ref "C3") (pin "2") (pinfunction "2_2") (pintype "passive"))
      (node (ref "C30") (pin "1") (pinfunction "1_1") (pintype "passive"))
      (node (ref "C31") (pin "2") (pinfunction "2_2") (pintype "passive"))
      (node (ref "C32") (pin "1") (pinfunction "1_1") (pintype "passive"))
      (node (ref "C33") (pin "2") (pinfunction "2_2") (pintype "passive"))
      (node (ref "C34") (pin "2") (pinfunction "2_2") (pintype "passive"))
      (node (ref "C35") (pin "2") (pinfunction "2_2") (pintype "passive"))
      (node (ref "C36") (pin "2") (pinfunction "2_2") (pintype "passive"))
      (node (ref "C38") (pin "2") (pinfunction "2_2") (pintype "passive"))
      (node (ref "C39") (pin "1") (pinfunction "1_1") (pintype "passive"))
      (node (ref "C4") (pin "2") (pinfunction "2_2") (pintype "passive"))
      (node (ref "C40") (pin "2") (pinfunction "2_2") (pintype "passive"))
      (node (ref "C41") (pin "2") (pinfunction "2_2") (pintype "passive"))
      (node (ref "C42") (pin "2") (pinfunction "2_2") (pintype "passive"))
      (node (ref "C43") (pin "1") (pinfunction "1_1") (pintype "passive"))
      (node (ref "C44") (pin "1") (pinfunction "1_1") (pintype "passive"))
      (node (ref "C45") (pin "-") (pinfunction "-_-") (pintype "passive"))
      (node (ref "C47") (pin "1") (pinfunction "1_1") (pintype "passive"))
      (node (ref "C5") (pin "2") (pinfunction "2_2") (pintype "passive"))
      (node (ref "C6") (pin "2") (pinfunction "2_2") (pintype "passive"))
      (node (ref "C7") (pin "2") (pinfunction "2_2") (pintype "passive"))
      (node (ref "C8") (pin "-") (pinfunction "-_-") (pintype "passive"))
      (node (ref "C9") (pin "2") (pinfunction "2_2") (pintype "passive"))
      (node (ref "D2") (pin "A") (pinfunction "A_A") (pintype "passive"))
      (node (ref "IC1") (pin "3") (pinfunction "GND_3") (pintype "power_in"))
      (node (ref "IC1") (pin "5") (pinfunction "~{ON}/OFF_5") (pintype "input"))
      (node (ref "IC2A") (pin "4") (pinfunction "GND_4") (pintype "power_in"))
      (node (ref "IC2B") (pin "4") (pinfunction "GND_4") (pintype "power_in"))
      (node (ref "IC3") (pin "2") (pinfunction "GND_2") (pintype "power_in"))
      (node (ref "IC3") (pin "8") (pinfunction "STB_8") (pintype "input"))
      (node (ref "IC4") (pin "12") (pinfunction "VSSA_12") (pintype "passive"))
      (node (ref "IC4") (pin "18") (pinfunction "VSS_4_18") (pintype "passive"))
      (node (ref "IC4") (pin "31") (pinfunction "VSS_1_31") (pintype "passive"))
      (node (ref "IC4") (pin "47") (pinfunction "VSS_2_47") (pintype "passive"))
      (node (ref "IC4") (pin "60") (pinfunction "BOOT0_60") (pintype "input"))
      (node (ref "IC4") (pin "63") (pinfunction "VSS_3_63") (pintype "passive"))
      (node (ref "IC5") (pin "2") (pinfunction "GND_2") (pintype "bidirectional"))
      (node (ref "IC6") (pin "8") (pinfunction "GND_8") (pintype "power_in"))
      (node (ref "IC7") (pin "12") (pinfunction "GND_12") (pintype "bidirectional"))
      (node (ref "IC8") (pin "1") (pinfunction "GND_1") (pintype "power_in"))
      (node (ref "IC9A") (pin "2") (pinfunction "GND_2") (pintype "bidirectional"))
      (node (ref "IC9B") (pin "7") (pinfunction "GND_7") (pintype "power_in"))
      (node (ref "JP1") (pin "2") (pinfunction "2_2") (pintype "passive"))
      (node (ref "JP2") (pin "23") (pinfunction "23_23") (pintype "passive"))
      (node (ref "JP3") (pin "12") (pinfunction "12_12") (pintype "passive"))
      (node (ref "JP3") (pin "4") (pinfunction "4_4") (pintype "passive"))
      (node (ref "JP3") (pin "8") (pinfunction "8_8") (pintype "passive"))
      (node (ref "JP6") (pin "3") (pinfunction "3_3") (pintype "passive"))
      (node (ref "JP6") (pin "5") (pinfunction "5_5") (pintype "passive"))
      (node (ref "JP7") (pin "10") (pinfunction "10_10") (pintype "passive"))
      (node (ref "JP7") (pin "15") (pinfunction "15_15") (pintype "passive"))
      (node (ref "JP7") (pin "16") (pinfunction "16_16") (pintype "passive"))
      (node (ref "JP7") (pin "5") (pinfunction "5_5") (pintype "passive"))
      (node (ref "JP7") (pin "7") (pinfunction "7_7") (pintype "passive"))
      (node (ref "PAD1") (pin "1") (pinfunction "P_1") (pintype "passive"))
      (node (ref "PAD3") (pin "1") (pinfunction "P_1") (pintype "passive"))
      (node (ref "PAD6") (pin "1") (pinfunction "P_1") (pintype "passive"))
      (node (ref "PWR") (pin "C") (pinfunction "C_C") (pintype "passive"))
      (node (ref "R1") (pin "1") (pinfunction "1_1") (pintype "passive"))
      (node (ref "R10") (pin "2") (pinfunction "2_2") (pintype "passive"))
      (node (ref "R12") (pin "2") (pinfunction "2_2") (pintype "passive"))
      (node (ref "R13") (pin "2") (pinfunction "2_2") (pintype "passive"))
      (node (ref "R14") (pin "1") (pinfunction "1_1") (pintype "passive"))
      (node (ref "R16") (pin "2") (pinfunction "2_2") (pintype "passive"))
      (node (ref "R19") (pin "2") (pinfunction "2_2") (pintype "passive"))
      (node (ref "R22") (pin "1") (pinfunction "1_1") (pintype "passive"))
      (node (ref "R23") (pin "2") (pinfunction "2_2") (pintype "passive"))
      (node (ref "R26") (pin "2") (pinfunction "2_2") (pintype "passive"))
      (node (ref "R27") (pin "2") (pinfunction "2_2") (pintype "passive"))
      (node (ref "R29") (pin "2") (pinfunction "2_2") (pintype "passive"))
      (node (ref "R36") (pin "1") (pinfunction "1_1") (pintype "passive"))
      (node (ref "R46") (pin "1") (pinfunction "1_1") (pintype "passive"))
      (node (ref "R50") (pin "1") (pinfunction "1_1") (pintype "passive"))
      (node (ref "R51") (pin "2") (pinfunction "2_2") (pintype "passive"))
    )
    (net (code "69") (name "Net-(ALIVE-PadA)") (class "Default")
      (node (ref "ALIVE") (pin "A") (pinfunction "A_A") (pintype "passive"))
      (node (ref "R33") (pin "2") (pinfunction "2_2") (pintype "passive"))
    )
    (net (code "70") (name "Net-(C1-Pad1)") (class "Default")
      (node (ref "C1") (pin "1") (pinfunction "1_1") (pintype "passive"))
      (node (ref "JP2") (pin "2") (pinfunction "2_2") (pintype "passive"))
      (node (ref "R1") (pin "2") (pinfunction "2_2") (pintype "passive"))
      (node (ref "R11") (pin "1") (pinfunction "1_1") (pintype "passive"))
    )
    (net (code "71") (name "Net-(C34-Pad1)") (class "Default")
      (node (ref "C34") (pin "1") (pinfunction "1_1") (pintype "passive"))
      (node (ref "R41") (pin "2") (pinfunction "2_2") (pintype "passive"))
      (node (ref "R42") (pin "1") (pinfunction "1_1") (pintype "passive"))
    )
    (net (code "72") (name "Net-(C35-Pad1)") (class "Default")
      (node (ref "C35") (pin "1") (pinfunction "1_1") (pintype "passive"))
      (node (ref "R42") (pin "2") (pinfunction "2_2") (pintype "passive"))
      (node (ref "R44") (pin "1") (pinfunction "1_1") (pintype "passive"))
    )
    (net (code "73") (name "Net-(C36-Pad1)") (class "Default")
      (node (ref "C36") (pin "1") (pinfunction "1_1") (pintype "passive"))
      (node (ref "C37") (pin "1") (pinfunction "1_1") (pintype "passive"))
      (node (ref "R44") (pin "2") (pinfunction "2_2") (pintype "passive"))
    )
    (net (code "74") (name "Net-(C44-Pad2)") (class "Default")
      (node (ref "C44") (pin "2") (pinfunction "2_2") (pintype "passive"))
      (node (ref "C47") (pin "2") (pinfunction "2_2") (pintype "passive"))
      (node (ref "R52") (pin "1") (pinfunction "1_1") (pintype "passive"))
    )
    (net (code "75") (name "Net-(D3-A)") (class "Default")
      (node (ref "D3") (pin "2") (pinfunction "A_2") (pintype "passive"))
      (node (ref "IC5") (pin "1") (pinfunction "SW_1") (pintype "bidirectional"))
      (node (ref "JP13") (pin "1") (pinfunction "P_1") (pintype "passive"))
      (node (ref "L4") (pin "2") (pinfunction "2_2") (pintype "passive"))
    )
    (net (code "76") (name "Net-(D3-C)") (class "Default")
      (node (ref "C43") (pin "2") (pinfunction "2_2") (pintype "passive"))
      (node (ref "C45") (pin "+") (pinfunction "+_+") (pintype "passive"))
      (node (ref "D3") (pin "1") (pinfunction "C_1") (pintype "passive"))
      (node (ref "IC2A") (pin "2") (pinfunction "SUPPLY_VOLTAGE_2") (pintype "bidirectional"))
      (node (ref "IC2B") (pin "6") (pinfunction "VS_6") (pintype "power_in"))
      (node (ref "PAD5") (pin "1") (pinfunction "P_1") (pintype "passive"))
      (node (ref "R35") (pin "2") (pinfunction "2_2") (pintype "passive"))
    )
    (net (code "77") (name "Net-(IC1-OUT)") (class "Default")
      (node (ref "D2") (pin "C") (pinfunction "C_C") (pintype "passive"))
      (node (ref "IC1") (pin "2") (pinfunction "OUT_2") (pintype "output"))
      (node (ref "L2") (pin "2") (pinfunction "2_2") (pintype "passive"))
      (node (ref "L5") (pin "1") (pinfunction "1_1") (pintype "passive"))
    )
    (net (code "78") (name "Net-(IC1-VIN)") (class "Default")
      (node (ref "C10") (pin "1") (pinfunction "1_1") (pintype "passive"))
      (node (ref "C8") (pin "+") (pinfunction "+_+") (pintype "passive"))
      (node (ref "D1") (pin "C") (pinfunction "C_C") (pintype "passive"))
      (node (ref "IC1") (pin "1") (pinfunction "VIN_1") (pintype "input"))
      (node (ref "PAD2") (pin "1") (pinfunction "P_1") (pintype "passive"))
    )
    (net (code "79") (name "Net-(IC2A-IN1+)") (class "Default")
      (node (ref "C37") (pin "2") (pinfunction "2_2") (pintype "passive"))
      (node (ref "IC2A") (pin "7") (pinfunction "IN1+_7") (pintype "input"))
      (node (ref "IC2B") (pin "3") (pinfunction "+IN_3") (pintype "input"))
      (node (ref "R46") (pin "2") (pinfunction "2_2") (pintype "passive"))
    )
    (net (code "80") (name "Net-(IC2A-IN1-)") (class "Default")
      (node (ref "C39") (pin "2") (pinfunction "2_2") (pintype "passive"))
      (node (ref "IC2A") (pin "8") (pinfunction "IN1-_8") (pintype "input"))
      (node (ref "IC2B") (pin "2") (pinfunction "-IN_2") (pintype "input"))
    )
    (net (code "81") (name "Net-(IC2A-OUT1)") (class "Default")
      (node (ref "C46") (pin "1") (pinfunction "1_1") (pintype "passive"))
      (node (ref "IC2A") (pin "1") (pinfunction "OUT1_1") (pintype "output"))
      (node (ref "IC2B") (pin "5") (pinfunction "OUT_5") (pintype "output"))
      (node (ref "R52") (pin "2") (pinfunction "2_2") (pintype "passive"))
    )
    (net (code "82") (name "Net-(IC4-PD0_OSC_IN)") (class "Default")
      (node (ref "C26") (pin "1") (pinfunction "1_1") (pintype "passive"))
      (node (ref "IC4") (pin "5") (pinfunction "PD0_OSC_IN_5") (pintype "bidirectional"))
      (node (ref "JP16") (pin "1") (pinfunction "P_1") (pintype "passive"))
      (node (ref "Q1") (pin "2") (pinfunction "2_2") (pintype "passive"))
    )
    (net (code "83") (name "Net-(IC4-PD1_OSC_OUT)") (class "Default")
      (node (ref "C27") (pin "1") (pinfunction "1_1") (pintype "passive"))
      (node (ref "IC4") (pin "6") (pinfunction "PD1_OSC_OUT_6") (pintype "bidirectional"))
      (node (ref "JP17") (pin "1") (pinfunction "P_1") (pintype "passive"))
      (node (ref "Q1") (pin "1") (pinfunction "1_1") (pintype "passive"))
    )
    (net (code "84") (name "Net-(IC4-VDDA)") (class "Default")
      (node (ref "C24") (pin "1") (pinfunction "1_1") (pintype "passive"))
      (node (ref "IC4") (pin "13") (pinfunction "VDDA_13") (pintype "power_in"))
      (node (ref "JP11") (pin "1") (pinfunction "P_1") (pintype "passive"))
      (node (ref "L3") (pin "1") (pinfunction "1_1") (pintype "passive"))
    )
    (net (code "85") (name "Net-(IC5-FB)") (class "Default")
      (node (ref "IC5") (pin "3") (pinfunction "FB_3") (pintype "bidirectional"))
      (node (ref "R35") (pin "1") (pinfunction "1_1") (pintype "passive"))
      (node (ref "R36") (pin "2") (pinfunction "2_2") (pintype "passive"))
    )
    (net (code "86") (name "Net-(IC6-CD+)") (class "Default")
      (node (ref "IC6") (pin "9") (pinfunction "CD+_9") (pintype "passive"))
      (node (ref "JP8") (pin "1") (pinfunction "1_1") (pintype "passive"))
    )
    (net (code "87") (name "Net-(IC7-+INC)") (class "Default")
      (node (ref "C33") (pin "1") (pinfunction "1_1") (pintype "passive"))
      (node (ref "IC7") (pin "11") (pinfunction "+IND_11") (pintype "bidirectional"))
      (node (ref "IC7") (pin "9") (pinfunction "+INC_9") (pintype "bidirectional"))
      (node (ref "R38") (pin "2") (pinfunction "2_2") (pintype "passive"))
    )
    (net (code "88") (name "Net-(IC7--INA)") (class "Default")
      (node (ref "C32") (pin "2") (pinfunction "2_2") (pintype "passive"))
      (node (ref "IC7") (pin "4") (pinfunction "-INA_4") (pintype "bidirectional"))
      (node (ref "IC7") (pin "6") (pinfunction "-INB_6") (pintype "bidirectional"))
      (node (ref "R37") (pin "2") (pinfunction "2_2") (pintype "passive"))
    )
    (net (code "89") (name "Net-(JP7-Pad4)") (class "Default")
      (node (ref "JP7") (pin "4") (pinfunction "4_4") (pintype "passive"))
      (node (ref "R47") (pin "1") (pinfunction "1_1") (pintype "passive"))
    )
    (net (code "90") (name "Net-(JP7-Pad6)") (class "Default")
      (node (ref "JP7") (pin "6") (pinfunction "6_6") (pintype "passive"))
      (node (ref "R48") (pin "1") (pinfunction "1_1") (pintype "passive"))
    )
    (net (code "91") (name "Net-(JP7-Pad9)") (class "Default")
      (node (ref "JP7") (pin "9") (pinfunction "9_9") (pintype "passive"))
      (node (ref "R49") (pin "2") (pinfunction "2_2") (pintype "passive"))
    )
    (net (code "92") (name "Net-(JP7-Pad13)") (class "Default")
      (node (ref "JP7") (pin "13") (pinfunction "13_13") (pintype "passive"))
      (node (ref "R39") (pin "1") (pinfunction "1_1") (pintype "passive"))
    )
    (net (code "93") (name "Net-(JP15-P)") (class "Default")
      (node (ref "C2") (pin "1") (pinfunction "1_1") (pintype "passive"))
      (node (ref "JP1") (pin "1") (pinfunction "1_1") (pintype "passive"))
      (node (ref "JP15") (pin "1") (pinfunction "P_1") (pintype "passive"))
      (node (ref "L1") (pin "2") (pinfunction "2_2") (pintype "passive"))
    )
    (net (code "94") (name "Net-(PWR-PadA)") (class "Default")
      (node (ref "PWR") (pin "A") (pinfunction "A_A") (pintype "passive"))
      (node (ref "R32") (pin "2") (pinfunction "2_2") (pintype "passive"))
    )
    (net (code "95") (name "Net-(R40-Pad2)") (class "Default")
      (node (ref "R40") (pin "2") (pinfunction "2_2") (pintype "passive"))
      (node (ref "R41") (pin "1") (pinfunction "1_1") (pintype "passive"))
    )
    (net (code "96") (name "VCC") (class "Default")
      (node (ref "C19") (pin "1") (pinfunction "1_1") (pintype "passive"))
      (node (ref "C20") (pin "+") (pinfunction "+_+") (pintype "passive"))
      (node (ref "C28") (pin "1") (pinfunction "1_1") (pintype "passive"))
      (node (ref "IC1") (pin "4") (pinfunction "FB_4") (pintype "input"))
      (node (ref "IC3") (pin "3") (pinfunction "VCC_3") (pintype "power_in"))
      (node (ref "IC5") (pin "4") (pinfunction "EN_4") (pintype "bidirectional"))
      (node (ref "IC5") (pin "5") (pinfunction "VIN_5") (pintype "bidirectional"))
      (node (ref "IC7") (pin "3") (pinfunction "VCC_3") (pintype "bidirectional"))
      (node (ref "IC8") (pin "3") (pinfunction "VIN_3") (pintype "input"))
      (node (ref "JP12") (pin "1") (pinfunction "P_1") (pintype "passive"))
      (node (ref "JP3") (pin "1") (pinfunction "1_1") (pintype "passive"))
      (node (ref "JP3") (pin "5") (pinfunction "5_5") (pintype "passive"))
      (node (ref "JP3") (pin "9") (pinfunction "9_9") (pintype "passive"))
      (node (ref "JP7") (pin "1") (pinfunction "1_1") (pintype "passive"))
      (node (ref "JP7") (pin "11") (pinfunction "11_11") (pintype "passive"))
      (node (ref "JP7") (pin "12") (pinfunction "12_12") (pintype "passive"))
      (node (ref "JP7") (pin "2") (pinfunction "2_2") (pintype "passive"))
      (node (ref "JP7") (pin "8") (pinfunction "8_8") (pintype "passive"))
      (node (ref "L2") (pin "1") (pinfunction "1_1") (pintype "passive"))
      (node (ref "L4") (pin "1") (pinfunction "1_1") (pintype "passive"))
      (node (ref "L5") (pin "2") (pinfunction "2_2") (pintype "passive"))
      (node (ref "PAD4") (pin "1") (pinfunction "P_1") (pintype "passive"))
      (node (ref "R11") (pin "2") (pinfunction "2_2") (pintype "passive"))
      (node (ref "R15") (pin "2") (pinfunction "2_2") (pintype "passive"))
      (node (ref "R17") (pin "1") (pinfunction "1_1") (pintype "passive"))
      (node (ref "R18") (pin "1") (pinfunction "1_1") (pintype "passive"))
      (node (ref "R28") (pin "1") (pinfunction "1_1") (pintype "passive"))
      (node (ref "R43") (pin "2") (pinfunction "2_2") (pintype "passive"))
      (node (ref "R45") (pin "2") (pinfunction "2_2") (pintype "passive"))
    )
    (net (code "97") (name "VCCIO") (class "Default")
      (node (ref "C22") (pin "1") (pinfunction "1_1") (pintype "passive"))
      (node (ref "C23") (pin "2") (pinfunction "2_2") (pintype "passive"))
      (node (ref "C25") (pin "2") (pinfunction "2_2") (pintype "passive"))
      (node (ref "C29") (pin "2") (pinfunction "2_2") (pintype "passive"))
      (node (ref "C30") (pin "2") (pinfunction "2_2") (pintype "passive"))
      (node (ref "IC3") (pin "5") (pinfunction "SPLIT_5") (pintype "bidirectional"))
      (node (ref "IC4") (pin "1") (pinfunction "VBAT_1") (pintype "input"))
      (node (ref "IC4") (pin "19") (pinfunction "VDD_4_19") (pintype "power_in"))
      (node (ref "IC4") (pin "32") (pinfunction "VDD_1_32") (pintype "power_in"))
      (node (ref "IC4") (pin "48") (pinfunction "VDD_2_48") (pintype "power_in"))
      (node (ref "IC4") (pin "64") (pinfunction "VDD_3_64") (pintype "power_in"))
      (node (ref "IC8") (pin "2") (pinfunction "VOUT_2") (pintype "output"))
      (node (ref "IC9A") (pin "5") (pinfunction "VCC_5") (pintype "bidirectional"))
      (node (ref "IC9B") (pin "14") (pinfunction "VCC_14") (pintype "power_in"))
      (node (ref "JP10") (pin "1") (pinfunction "P_1") (pintype "passive"))
      (node (ref "JP14") (pin "1") (pinfunction "P_1") (pintype "passive"))
      (node (ref "JP6") (pin "1") (pinfunction "1_1") (pintype "passive"))
      (node (ref "L1") (pin "1") (pinfunction "1_1") (pintype "passive"))
      (node (ref "L3") (pin "2") (pinfunction "2_2") (pintype "passive"))
      (node (ref "R32") (pin "1") (pinfunction "1_1") (pintype "passive"))
      (node (ref "R33") (pin "1") (pinfunction "1_1") (pintype "passive"))
      (node (ref "R34") (pin "2") (pinfunction "2_2") (pintype "passive"))
    )
    (net (code "98") (name "unconnected-(IC2A-IN2+-Pad6)") (class "Default")
      (node (ref "IC2A") (pin "6") (pinfunction "IN2+_6") (pintype "input"))
    )
    (net (code "99") (name "unconnected-(IC2A-IN2--Pad5)") (class "Default")
      (node (ref "IC2A") (pin "5") (pinfunction "IN2-_5") (pintype "input"))
    )
    (net (code "100") (name "unconnected-(IC2A-OUT2-Pad3)") (class "Default")
      (node (ref "IC2A") (pin "3") (pinfunction "OUT2_3") (pintype "output"))
    )
    (net (code "101") (name "unconnected-(IC2B-BYPASS-Pad7)") (class "Default")
      (node (ref "IC2B") (pin "7") (pinfunction "BYPASS_7") (pintype "passive"))
    )
    (net (code "102") (name "unconnected-(IC2B-GAIN-Pad1)") (class "Default")
      (node (ref "IC2B") (pin "1") (pinfunction "GAIN_1") (pintype "passive"))
    )
    (net (code "103") (name "unconnected-(IC2B-GAIN-Pad8)") (class "Default")
      (node (ref "IC2B") (pin "8") (pinfunction "GAIN_8") (pintype "passive"))
    )
    (net (code "104") (name "unconnected-(IC4-PA0-WKUP-Pad14)") (class "Default")
      (node (ref "IC4") (pin "14") (pinfunction "PA0-WKUP_14") (pintype "bidirectional"))
    )
    (net (code "105") (name "unconnected-(IC4-PA15-Pad50)") (class "Default")
      (node (ref "IC4") (pin "50") (pinfunction "PA15_50") (pintype "bidirectional"))
    )
    (net (code "106") (name "unconnected-(IC4-PB2-Pad28)") (class "Default")
      (node (ref "IC4") (pin "28") (pinfunction "PB2_28") (pintype "bidirectional"))
    )
    (net (code "107") (name "unconnected-(IC4-PB3-Pad55)") (class "Default")
      (node (ref "IC4") (pin "55") (pinfunction "PB3_55") (pintype "bidirectional"))
    )
    (net (code "108") (name "unconnected-(IC4-PB4-Pad56)") (class "Default")
      (node (ref "IC4") (pin "56") (pinfunction "PB4_56") (pintype "bidirectional"))
    )
    (net (code "109") (name "unconnected-(IC4-PC14-OSC32_IN-Pad3)") (class "Default")
      (node (ref "IC4") (pin "3") (pinfunction "PC14-OSC32_IN_3") (pintype "bidirectional"))
    )
    (net (code "110") (name "unconnected-(IC4-PC15-OSC32_OUT-Pad4)") (class "Default")
      (node (ref "IC4") (pin "4") (pinfunction "PC15-OSC32_OUT_4") (pintype "bidirectional"))
    )
    (net (code "111") (name "unconnected-(IC9B-2A-Pad3)") (class "Default")
      (node (ref "IC9B") (pin "3") (pinfunction "2A_3") (pintype "bidirectional"))
    )
    (net (code "112") (name "unconnected-(IC9B-2B-Pad4)") (class "Default")
      (node (ref "IC9B") (pin "4") (pinfunction "2B_4") (pintype "bidirectional"))
    )
    (net (code "113") (name "unconnected-(IC9B-2C-Pad5)") (class "Default")
      (node (ref "IC9B") (pin "5") (pinfunction "2C_5") (pintype "bidirectional"))
    )
    (net (code "114") (name "unconnected-(IC9B-2Y-Pad6)") (class "Default")
      (node (ref "IC9B") (pin "6") (pinfunction "2Y_6") (pintype "bidirectional"))
    )
    (net (code "115") (name "unconnected-(IC9B-3A-Pad9)") (class "Default")
      (node (ref "IC9B") (pin "9") (pinfunction "3A_9") (pintype "bidirectional"))
    )
    (net (code "116") (name "unconnected-(IC9B-3B-Pad10)") (class "Default")
      (node (ref "IC9B") (pin "10") (pinfunction "3B_10") (pintype "bidirectional"))
    )
    (net (code "117") (name "unconnected-(IC9B-3C-Pad11)") (class "Default")
      (node (ref "IC9B") (pin "11") (pinfunction "3C_11") (pintype "bidirectional"))
    )
    (net (code "118") (name "unconnected-(IC9B-3Y-Pad8)") (class "Default")
      (node (ref "IC9B") (pin "8") (pinfunction "3Y_8") (pintype "bidirectional"))
    )
    (net (code "119") (name "unconnected-(JP1-Pad5)") (class "Default")
      (node (ref "JP1") (pin "5") (pinfunction "5_5") (pintype "passive"))
    )
    (net (code "120") (name "unconnected-(JP1-Pad6)") (class "Default")
      (node (ref "JP1") (pin "6") (pinfunction "6_6") (pintype "passive"))
    )
    (net (code "121") (name "unconnected-(JP1-Pad7)") (class "Default")
      (node (ref "JP1") (pin "7") (pinfunction "7_7") (pintype "passive"))
    )
    (net (code "122") (name "unconnected-(JP1-Pad8)") (class "Default")
      (node (ref "JP1") (pin "8") (pinfunction "8_8") (pintype "passive"))
    )
    (net (code "123") (name "unconnected-(JP1-Pad9)") (class "Default")
      (node (ref "JP1") (pin "9") (pinfunction "9_9") (pintype "passive"))
    )
    (net (code "124") (name "unconnected-(JP1-Pad10)") (class "Default")
      (node (ref "JP1") (pin "10") (pinfunction "10_10") (pintype "passive"))
    )
    (net (code "125") (name "unconnected-(JP3-Pad14)") (class "Default")
      (node (ref "JP3") (pin "14") (pinfunction "14_14") (pintype "passive"))
    )
    (net (code "126") (name "unconnected-(JP6-Pad6)") (class "Default")
      (node (ref "JP6") (pin "6") (pinfunction "6_6") (pintype "passive"))
    )
    (net (code "127") (name "unconnected-(JP6-Pad7)") (class "Default")
      (node (ref "JP6") (pin "7") (pinfunction "7_7") (pintype "passive"))
    )
    (net (code "128") (name "unconnected-(JP6-Pad8)") (class "Default")
      (node (ref "JP6") (pin "8") (pinfunction "8_8") (pintype "passive"))
    )
    (net (code "129") (name "unconnected-(JP6-Pad9)") (class "Default")
      (node (ref "JP6") (pin "9") (pinfunction "9_9") (pintype "passive"))
    )
    (net (code "130") (name "unconnected-(JP7-Pad3)") (class "Default")
      (node (ref "JP7") (pin "3") (pinfunction "3_3") (pintype "passive"))
    )
    (net (code "131") (name "unconnected-(JP7-Pad14)") (class "Default")
      (node (ref "JP7") (pin "14") (pinfunction "14_14") (pintype "passive"))
    )
    (net (code "132") (name "unconnected-(TP1-PadTP)") (class "Default")
      (node (ref "TP1") (pin "TP") (pinfunction "TP_TP") (pintype "input"))
    )
  )
)
